# Burglar_alarm.net
KiCad netlist of a schematic drawn in EAGLE
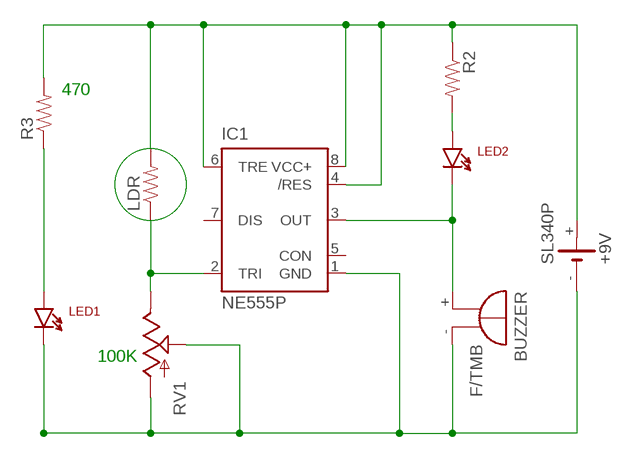
[diagram p0: schematic, sheet 1]

(export (version "E")
  (design (tool "Eeschema 10.0.6"))
  (components
    (comp (ref "+9V")
      (value "SL340P")
      (footprint "eagle-import:SL-340_P3.6V")
      (libsource (lib "eagle-import") (part "SL340P"))
    )
    (comp (ref "BUZZER")
      (value "F/TMB")
      (footprint "eagle-import:F_TMB")
      (libsource (lib "eagle-import") (part "F/TMB"))
    )
    (comp (ref "IC1")
      (value "NE555P")
      (footprint "eagle-import:DIL-08")
      (fields (field (name "MF") "Arrow Electronics") (field (name "MPN") "NE555N"))
      (libsource (lib "eagle-import") (part "NE555P"))
    )
    (comp (ref "LDR")
      (value "RESISTORAXIAL-0.3")
      (footprint "eagle-import:AXIAL-0.3")
      (libsource (lib "eagle-import") (part "RESISTORAXIAL-0.3"))
    )
    (comp (ref "LED1")
      (value "LTE-302")
      (footprint "eagle-import:LTE-302")
      (libsource (lib "eagle-import") (part "LTE-302"))
    )
    (comp (ref "LED2")
      (value "LTE-302")
      (footprint "eagle-import:LTE-302")
      (libsource (lib "eagle-import") (part "LTE-302"))
    )
    (comp (ref "R2")
      (value "RESISTORAXIAL-0.3")
      (footprint "eagle-import:AXIAL-0.3")
      (libsource (lib "eagle-import") (part "RESISTORAXIAL-0.3"))
    )
    (comp (ref "R3")
      (value "RESISTORAXIAL-0.3")
      (footprint "eagle-import:AXIAL-0.3")
      (libsource (lib "eagle-import") (part "RESISTORAXIAL-0.3"))
    )
    (comp (ref "RV1")
      (value "POTTRIM")
      (footprint "eagle-import:TRIM_POT")
      (libsource (lib "eagle-import") (part "POTTRIM"))
    )
  )
  (nets
    (net (code "1") (name "Net-(IC1-GND)") (class "Default")
      (node (ref "+9V") (pin "-") (pinfunction "-_-") (pintype "passive"))
      (node (ref "BUZZER") (pin "-") (pinfunction "-_-") (pintype "passive"))
      (node (ref "IC1") (pin "1") (pinfunction "GND_1") (pintype "power_in"))
      (node (ref "LED1") (pin "C") (pinfunction "C_C") (pintype "bidirectional"))
      (node (ref "RV1") (pin "1") (pinfunction "S_1") (pintype "passive"))
      (node (ref "RV1") (pin "3") (pinfunction "A_3") (pintype "passive"))
    )
    (net (code "2") (name "Net-(IC1-OUT)") (class "Default")
      (node (ref "BUZZER") (pin "+") (pinfunction "+_+") (pintype "passive"))
      (node (ref "IC1") (pin "3") (pinfunction "OUT_3") (pintype "output"))
      (node (ref "LED2") (pin "C") (pinfunction "C_C") (pintype "bidirectional"))
    )
    (net (code "3") (name "Net-(IC1-TRE)") (class "Default")
      (node (ref "+9V") (pin "+") (pinfunction "+_+") (pintype "passive"))
      (node (ref "IC1") (pin "4") (pinfunction "/RES_4") (pintype "input"))
      (node (ref "IC1") (pin "6") (pinfunction "TRE_6") (pintype "input"))
      (node (ref "IC1") (pin "8") (pinfunction "VCC+_8") (pintype "power_in"))
      (node (ref "LDR") (pin "P$2") (pinfunction "2_P$2") (pintype "passive"))
      (node (ref "R2") (pin "P$1") (pinfunction "1_P$1") (pintype "passive"))
      (node (ref "R3") (pin "P$2") (pinfunction "2_P$2") (pintype "passive"))
    )
    (net (code "4") (name "Net-(IC1-TRI)") (class "Default")
      (node (ref "IC1") (pin "2") (pinfunction "TRI_2") (pintype "input"))
      (node (ref "LDR") (pin "P$1") (pinfunction "1_P$1") (pintype "passive"))
      (node (ref "RV1") (pin "2") (pinfunction "E_2") (pintype "passive"))
    )
    (net (code "5") (name "Net-(R2-2)") (class "Default")
      (node (ref "LED2") (pin "A") (pinfunction "A_A") (pintype "bidirectional"))
      (node (ref "R2") (pin "P$2") (pinfunction "2_P$2") (pintype "passive"))
    )
    (net (code "6") (name "Net-(R3-1)") (class "Default")
      (node (ref "LED1") (pin "A") (pinfunction "A_A") (pintype "bidirectional"))
      (node (ref "R3") (pin "P$1") (pinfunction "1_P$1") (pintype "passive"))
    )
    (net (code "7") (name "unconnected-(IC1-CON-Pad5)") (class "Default")
      (node (ref "IC1") (pin "5") (pinfunction "CON_5") (pintype "input"))
    )
    (net (code "8") (name "unconnected-(IC1-DIS-Pad7)") (class "Default")
      (node (ref "IC1") (pin "7") (pinfunction "DIS_7") (pintype "input"))
    )
  )
)
